# 5vldo.net
KiCad netlist of a schematic drawn in EAGLE
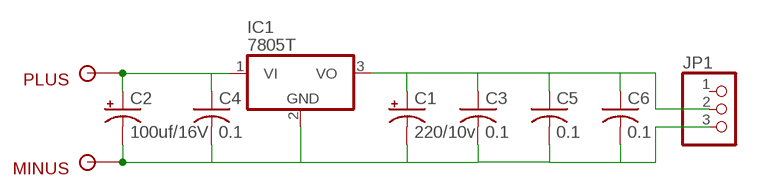
[diagram p0: schematic, sheet 1]

(export (version "E")
  (design (tool "Eeschema 10.0.6"))
  (components
    (comp (ref "C1")
      (value "220/10v")
      (footprint "eagle-import:SMC_B")
      (libsource (lib "eagle-import") (part "CPOL-USSMCB"))
    )
    (comp (ref "C2")
      (value "100uf/16V")
      (footprint "eagle-import:SMC_B")
      (libsource (lib "eagle-import") (part "CPOL-USSMCB"))
    )
    (comp (ref "C3")
      (value "0.1")
      (footprint "eagle-import:C0805")
      (libsource (lib "eagle-import") (part "C-USC0805"))
    )
    (comp (ref "C4")
      (value "0.1")
      (footprint "eagle-import:C0805")
      (libsource (lib "eagle-import") (part "C-USC0805"))
    )
    (comp (ref "C5")
      (value "0.1")
      (footprint "eagle-import:C0805")
      (libsource (lib "eagle-import") (part "C-USC0805"))
    )
    (comp (ref "C6")
      (value "0.1")
      (footprint "eagle-import:C0805")
      (libsource (lib "eagle-import") (part "C-USC0805"))
    )
    (comp (ref "IC1")
      (value "7805T")
      (footprint "eagle-import:TO220H")
      (libsource (lib "eagle-import") (part "78T05"))
    )
    (comp (ref "JP1")
      (value "PINHD-1X3")
      (footprint "eagle-import:1X03")
      (libsource (lib "eagle-import") (part "PINHD-1X3"))
    )
    (comp (ref "MINUS")
      (value "SOLDER_POINTD")
      (footprint "eagle-import:P1-17Y")
      (libsource (lib "eagle-import") (part "SOLDER_POINTD"))
    )
    (comp (ref "PLUS")
      (value "SOLDER_POINTD")
      (footprint "eagle-import:P1-17Y")
      (libsource (lib "eagle-import") (part "SOLDER_POINTD"))
    )
  )
  (nets
    (net (code "1") (name "Net-(IC1-GND)") (class "Default")
      (node (ref "C1") (pin "-") (pinfunction "-_-") (pintype "passive"))
      (node (ref "C2") (pin "-") (pinfunction "-_-") (pintype "passive"))
      (node (ref "C3") (pin "2") (pinfunction "2_2") (pintype "passive"))
      (node (ref "C4") (pin "2") (pinfunction "2_2") (pintype "passive"))
      (node (ref "C5") (pin "2") (pinfunction "2_2") (pintype "passive"))
      (node (ref "C6") (pin "2") (pinfunction "2_2") (pintype "passive"))
      (node (ref "IC1") (pin "2") (pinfunction "GND_2") (pintype "passive"))
      (node (ref "JP1") (pin "3") (pinfunction "3_3") (pintype "passive"))
      (node (ref "MINUS") (pin "1") (pinfunction "P$1_1") (pintype "bidirectional"))
    )
    (net (code "2") (name "Net-(IC1-VI)") (class "Default")
      (node (ref "C2") (pin "+") (pinfunction "+_+") (pintype "passive"))
      (node (ref "C4") (pin "1") (pinfunction "1_1") (pintype "passive"))
      (node (ref "IC1") (pin "1") (pinfunction "VI_1") (pintype "input"))
      (node (ref "PLUS") (pin "1") (pinfunction "P$1_1") (pintype "bidirectional"))
    )
    (net (code "3") (name "Net-(IC1-VO)") (class "Default")
      (node (ref "C1") (pin "+") (pinfunction "+_+") (pintype "passive"))
      (node (ref "C3") (pin "1") (pinfunction "1_1") (pintype "passive"))
      (node (ref "C5") (pin "1") (pinfunction "1_1") (pintype "passive"))
      (node (ref "C6") (pin "1") (pinfunction "1_1") (pintype "passive"))
      (node (ref "IC1") (pin "3") (pinfunction "VO_3") (pintype "passive"))
      (node (ref "JP1") (pin "2") (pinfunction "2_2") (pintype "passive"))
    )
    (net (code "4") (name "unconnected-(JP1-Pad1)") (class "Default")
      (node (ref "JP1") (pin "1") (pinfunction "1_1") (pintype "passive"))
    )
  )
)
